# MCU_Module_V3.net
KiCad netlist of a schematic drawn in EAGLE
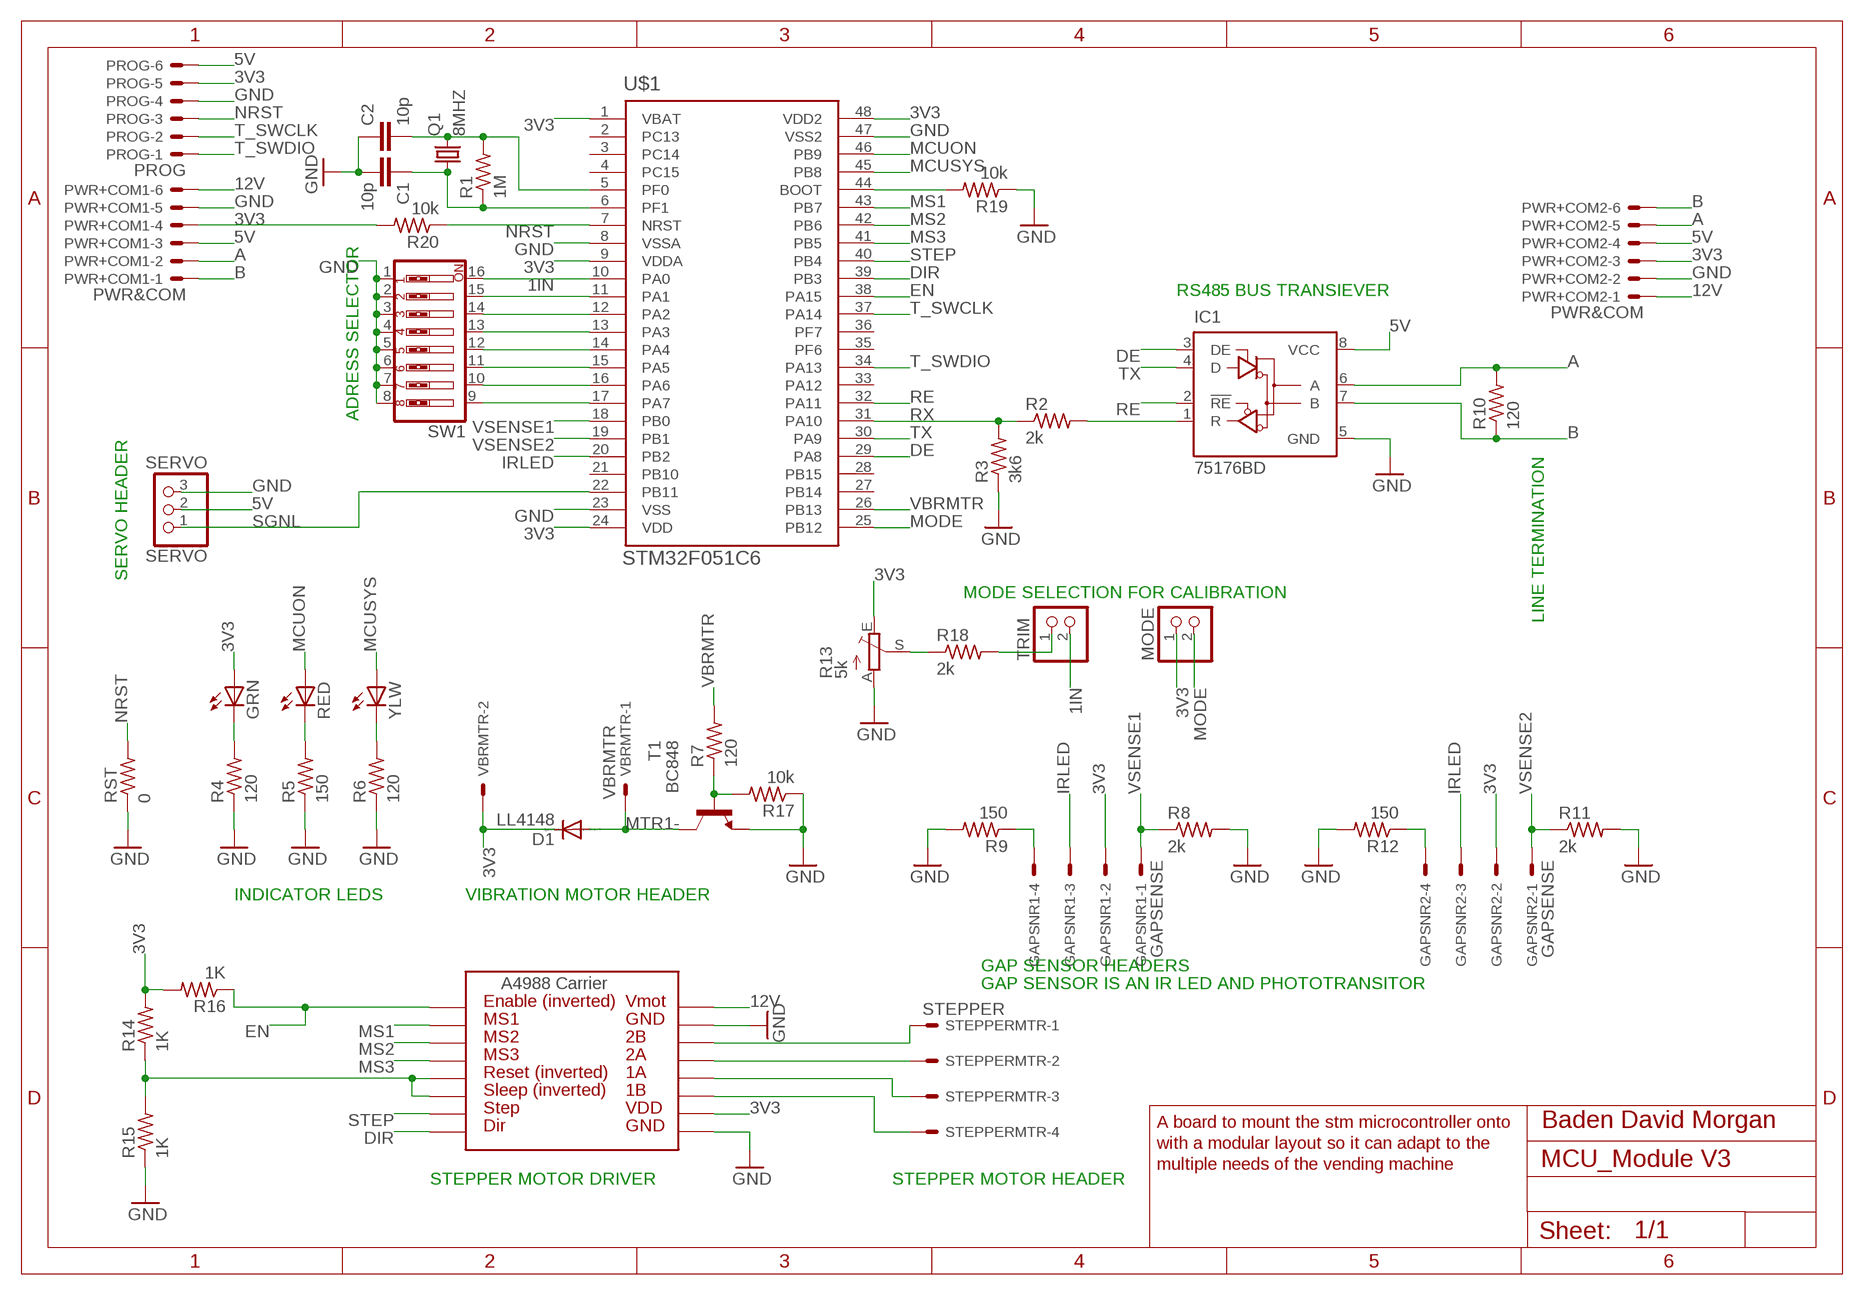
[diagram p0: schematic, sheet 1]

(export (version "E")
  (design (tool "Eeschema 10.0.6"))
  (components
    (comp (ref "C1")
      (value "10p")
      (footprint "eagle-import:C0805")
      (libsource (lib "eagle-import") (part "C-EUC0805"))
    )
    (comp (ref "C2")
      (value "10p")
      (footprint "eagle-import:C0805")
      (libsource (lib "eagle-import") (part "C-EUC0805"))
    )
    (comp (ref "D1")
      (value "LL4148")
      (footprint "eagle-import:SOD80C")
      (libsource (lib "eagle-import") (part "PMLL4150"))
    )
    (comp (ref "GAPSNR1")
      (value "GAPSENSE")
      (footprint "eagle-import:6410-04")
      (libsource (lib "eagle-import") (part "22-?-0427-2041"))
    )
    (comp (ref "GAPSNR2")
      (value "GAPSENSE")
      (footprint "eagle-import:6410-04")
      (libsource (lib "eagle-import") (part "22-?-0427-2041"))
    )
    (comp (ref "GRN")
      (value "LEDSML1206")
      (footprint "eagle-import:SML1206")
      (libsource (lib "eagle-import") (part "LEDSML1206"))
    )
    (comp (ref "IC1")
      (value "75176BD")
      (footprint "eagle-import:D_R-PDSO-G8")
      (libsource (lib "eagle-import") (part "75176AD"))
    )
    (comp (ref "MODE")
      (value "PINHD-1X2")
      (footprint "eagle-import:1X02")
      (libsource (lib "eagle-import") (part "PINHD-1X2"))
    )
    (comp (ref "PROG")
      (value "PROG")
      (footprint "eagle-import:6410-06")
      (libsource (lib "eagle-import") (part "22-?-0627-2061"))
    )
    (comp (ref "PWR+COM1")
      (value "PWR&COM")
      (footprint "eagle-import:7395-06")
      (libsource (lib "eagle-import") (part "22-?-0605-7068"))
    )
    (comp (ref "PWR+COM2")
      (value "PWR&COM")
      (footprint "eagle-import:7395-06")
      (libsource (lib "eagle-import") (part "22-?-0605-7068"))
    )
    (comp (ref "Q1")
      (value "8MHZ")
      (footprint "eagle-import:SM49")
      (libsource (lib "eagle-import") (part "CRYSTALSM49"))
    )
    (comp (ref "R1")
      (value "1M")
      (footprint "eagle-import:R0805")
      (libsource (lib "eagle-import") (part "R-US_R0805"))
    )
    (comp (ref "R2")
      (value "2k")
      (footprint "eagle-import:R0805")
      (libsource (lib "eagle-import") (part "resistor_R-US_R0805"))
    )
    (comp (ref "R3")
      (value "3k6")
      (footprint "eagle-import:R0805")
      (libsource (lib "eagle-import") (part "resistor_R-US_R0805"))
    )
    (comp (ref "R4")
      (value "120")
      (footprint "eagle-import:R0805")
      (libsource (lib "eagle-import") (part "R-US_R0805"))
    )
    (comp (ref "R5")
      (value "150")
      (footprint "eagle-import:R0805")
      (libsource (lib "eagle-import") (part "R-US_R0805"))
    )
    (comp (ref "R6")
      (value "120")
      (footprint "eagle-import:R0805")
      (libsource (lib "eagle-import") (part "R-US_R0805"))
    )
    (comp (ref "R7")
      (value "120")
      (footprint "eagle-import:R0805")
      (libsource (lib "eagle-import") (part "R-US_R0805"))
    )
    (comp (ref "R8")
      (value "2k")
      (footprint "eagle-import:R0805")
      (libsource (lib "eagle-import") (part "resistor_R-US_R0805"))
    )
    (comp (ref "R9")
      (value "150")
      (footprint "eagle-import:R0805")
      (libsource (lib "eagle-import") (part "R-US_R0805"))
    )
    (comp (ref "R10")
      (value "120")
      (footprint "eagle-import:R0805")
      (libsource (lib "eagle-import") (part "resistor_R-US_R0805"))
    )
    (comp (ref "R11")
      (value "2k")
      (footprint "eagle-import:R0805")
      (libsource (lib "eagle-import") (part "resistor_R-US_R0805"))
    )
    (comp (ref "R12")
      (value "150")
      (footprint "eagle-import:R0805")
      (libsource (lib "eagle-import") (part "R-US_R0805"))
    )
    (comp (ref "R13")
      (value "5k")
      (footprint "eagle-import:B25P")
      (libsource (lib "eagle-import") (part "TRIM_EU-B25P"))
    )
    (comp (ref "R14")
      (value "1K")
      (footprint "eagle-import:R0805")
      (libsource (lib "eagle-import") (part "R-US_R0805"))
    )
    (comp (ref "R15")
      (value "1K")
      (footprint "eagle-import:R0805")
      (libsource (lib "eagle-import") (part "R-US_R0805"))
    )
    (comp (ref "R16")
      (value "1K")
      (footprint "eagle-import:R0805")
      (libsource (lib "eagle-import") (part "R-US_R0805"))
    )
    (comp (ref "R17")
      (value "10k")
      (footprint "eagle-import:R0805")
      (libsource (lib "eagle-import") (part "R-US_R0805"))
    )
    (comp (ref "R18")
      (value "2k")
      (footprint "eagle-import:R0805")
      (libsource (lib "eagle-import") (part "resistor_R-US_R0805"))
    )
    (comp (ref "R19")
      (value "10k")
      (footprint "eagle-import:R0805")
      (libsource (lib "eagle-import") (part "R-US_R0805"))
    )
    (comp (ref "R20")
      (value "10k")
      (footprint "eagle-import:R0805")
      (libsource (lib "eagle-import") (part "R-US_R0805"))
    )
    (comp (ref "RED")
      (value "LEDSML1206")
      (footprint "eagle-import:SML1206")
      (libsource (lib "eagle-import") (part "LEDSML1206"))
    )
    (comp (ref "RST")
      (value "0")
      (footprint "eagle-import:R0805")
      (libsource (lib "eagle-import") (part "R-US_R0805"))
    )
    (comp (ref "SERVO")
      (value "SERVO")
      (footprint "eagle-import:1X03")
      (libsource (lib "eagle-import") (part "PINHD-1X3"))
    )
    (comp (ref "STEPPERMTR")
      (value "STEPPER")
      (footprint "eagle-import:6410-04")
      (libsource (lib "eagle-import") (part "22-?-0427-2041"))
    )
    (comp (ref "SW1")
      (value "SW_DIP-8")
      (footprint "eagle-import:EDG-08")
      (libsource (lib "eagle-import") (part "SW_DIP-8"))
    )
    (comp (ref "T1")
      (value "BC848")
      (footprint "eagle-import:SOT23")
      (libsource (lib "eagle-import") (part "BC848"))
    )
    (comp (ref "TRIM")
      (value "PINHD-1X2")
      (footprint "eagle-import:1X02")
      (libsource (lib "eagle-import") (part "PINHD-1X2"))
    )
    (comp (ref "U$1")
      (value "STM32F051C6")
      (footprint "eagle-import:QFP50P900X900X160-48N")
      (libsource (lib "eagle-import") (part "STM32F051C6"))
    )
    (comp (ref "U$2")
      (value "A4983CARRIER")
      (footprint "eagle-import:A4988BREAKOUT")
      (libsource (lib "eagle-import") (part "A4983CARRIER"))
    )
    (comp (ref "VBRMTR")
      (value "VBRMTR")
      (footprint "eagle-import:6410-02")
      (libsource (lib "eagle-import") (part "22-?-0227-2021"))
    )
    (comp (ref "YLW")
      (value "LEDSML1206")
      (footprint "eagle-import:SML1206")
      (libsource (lib "eagle-import") (part "LEDSML1206"))
    )
  )
  (nets
    (net (code "1") (name "/1IN") (class "Default")
      (node (ref "SW1") (pin "16") (pinfunction "16_16") (pintype "passive"))
      (node (ref "TRIM") (pin "2") (pinfunction "2_2") (pintype "passive"))
      (node (ref "U$1") (pin "10") (pinfunction "PA0_10") (pintype "bidirectional"))
    )
    (net (code "2") (name "/3V3") (class "Default")
      (node (ref "D1") (pin "C") (pinfunction "C_C") (pintype "passive"))
      (node (ref "GAPSNR1") (pin "2") (pinfunction "S_2") (pintype "passive"))
      (node (ref "GAPSNR2") (pin "2") (pinfunction "S_2") (pintype "passive"))
      (node (ref "GRN") (pin "A") (pinfunction "A_A") (pintype "passive"))
      (node (ref "MODE") (pin "1") (pinfunction "1_1") (pintype "passive"))
      (node (ref "PROG") (pin "5") (pinfunction "S_5") (pintype "passive"))
      (node (ref "PWR+COM1") (pin "4") (pinfunction "S_4") (pintype "passive"))
      (node (ref "PWR+COM2") (pin "3") (pinfunction "S_3") (pintype "passive"))
      (node (ref "R13") (pin "E") (pinfunction "E_E") (pintype "passive"))
      (node (ref "R14") (pin "2") (pinfunction "2_2") (pintype "passive"))
      (node (ref "R16") (pin "2") (pinfunction "2_2") (pintype "passive"))
      (node (ref "R20") (pin "2") (pinfunction "2_2") (pintype "passive"))
      (node (ref "U$1") (pin "1") (pinfunction "VBAT_1") (pintype "bidirectional"))
      (node (ref "U$1") (pin "24") (pinfunction "VDD_24") (pintype "bidirectional"))
      (node (ref "U$1") (pin "48") (pinfunction "VDD2_48") (pintype "bidirectional"))
      (node (ref "U$1") (pin "9") (pinfunction "VDDA_9") (pintype "bidirectional"))
      (node (ref "U$2") (pin "VDD") (pinfunction "VDD_VDD") (pintype "power_in"))
      (node (ref "VBRMTR") (pin "2") (pinfunction "S_2") (pintype "passive"))
    )
    (net (code "3") (name "/5V") (class "Default")
      (node (ref "IC1") (pin "8") (pinfunction "VCC_8") (pintype "power_in"))
      (node (ref "PROG") (pin "6") (pinfunction "S_6") (pintype "passive"))
      (node (ref "PWR+COM1") (pin "3") (pinfunction "S_3") (pintype "passive"))
      (node (ref "PWR+COM2") (pin "4") (pinfunction "S_4") (pintype "passive"))
      (node (ref "SERVO") (pin "2") (pinfunction "2_2") (pintype "passive"))
    )
    (net (code "4") (name "/12V") (class "Default")
      (node (ref "PWR+COM1") (pin "6") (pinfunction "S_6") (pintype "passive"))
      (node (ref "PWR+COM2") (pin "1") (pinfunction "S_1") (pintype "passive"))
      (node (ref "U$2") (pin "VMOT") (pinfunction "VMOT_VMOT") (pintype "power_in"))
    )
    (net (code "5") (name "/A") (class "Default")
      (node (ref "IC1") (pin "6") (pinfunction "A_6") (pintype "output"))
      (node (ref "PWR+COM1") (pin "2") (pinfunction "S_2") (pintype "passive"))
      (node (ref "PWR+COM2") (pin "5") (pinfunction "S_5") (pintype "passive"))
      (node (ref "R10") (pin "2") (pinfunction "2_2") (pintype "passive"))
    )
    (net (code "6") (name "/B") (class "Default")
      (node (ref "IC1") (pin "7") (pinfunction "B_7") (pintype "output"))
      (node (ref "PWR+COM1") (pin "1") (pinfunction "S_1") (pintype "passive"))
      (node (ref "PWR+COM2") (pin "6") (pinfunction "S_6") (pintype "passive"))
      (node (ref "R10") (pin "1") (pinfunction "1_1") (pintype "passive"))
    )
    (net (code "7") (name "/DE") (class "Default")
      (node (ref "IC1") (pin "3") (pinfunction "DE_3") (pintype "input"))
      (node (ref "U$1") (pin "29") (pinfunction "PA8_29") (pintype "bidirectional"))
    )
    (net (code "8") (name "/DIR") (class "Default")
      (node (ref "U$1") (pin "39") (pinfunction "PB3_39") (pintype "bidirectional"))
      (node (ref "U$2") (pin "DIR") (pinfunction "DIR_DIR") (pintype "input"))
    )
    (net (code "9") (name "/EN") (class "Default")
      (node (ref "R16") (pin "1") (pinfunction "1_1") (pintype "passive"))
      (node (ref "U$1") (pin "38") (pinfunction "PA15_38") (pintype "bidirectional"))
      (node (ref "U$2") (pin "EN") (pinfunction "EN_EN") (pintype "input"))
    )
    (net (code "10") (name "/IRLED") (class "Default")
      (node (ref "GAPSNR1") (pin "3") (pinfunction "S_3") (pintype "passive"))
      (node (ref "GAPSNR2") (pin "3") (pinfunction "S_3") (pintype "passive"))
      (node (ref "U$1") (pin "20") (pinfunction "PB2_20") (pintype "bidirectional"))
    )
    (net (code "11") (name "/MCUON") (class "Default")
      (node (ref "RED") (pin "A") (pinfunction "A_A") (pintype "passive"))
      (node (ref "U$1") (pin "46") (pinfunction "PB9_46") (pintype "bidirectional"))
    )
    (net (code "12") (name "/MCUSYS") (class "Default")
      (node (ref "U$1") (pin "45") (pinfunction "PB8_45") (pintype "bidirectional"))
      (node (ref "YLW") (pin "A") (pinfunction "A_A") (pintype "passive"))
    )
    (net (code "13") (name "/MODE") (class "Default")
      (node (ref "MODE") (pin "2") (pinfunction "2_2") (pintype "passive"))
      (node (ref "U$1") (pin "25") (pinfunction "PB12_25") (pintype "bidirectional"))
    )
    (net (code "14") (name "/MS1") (class "Default")
      (node (ref "U$1") (pin "43") (pinfunction "PB7_43") (pintype "bidirectional"))
      (node (ref "U$2") (pin "MS1") (pinfunction "MS1_MS1") (pintype "input"))
    )
    (net (code "15") (name "/MS2") (class "Default")
      (node (ref "U$1") (pin "42") (pinfunction "PB6_42") (pintype "bidirectional"))
      (node (ref "U$2") (pin "MS2") (pinfunction "MS2_MS2") (pintype "input"))
    )
    (net (code "16") (name "/MS3") (class "Default")
      (node (ref "U$1") (pin "41") (pinfunction "PB5_41") (pintype "bidirectional"))
      (node (ref "U$2") (pin "MS3") (pinfunction "MS3_MS3") (pintype "input"))
    )
    (net (code "17") (name "/MTR1-") (class "Default")
      (node (ref "D1") (pin "A") (pinfunction "A_A") (pintype "passive"))
      (node (ref "T1") (pin "3") (pinfunction "C_3") (pintype "passive"))
      (node (ref "VBRMTR") (pin "1") (pinfunction "S_1") (pintype "passive"))
    )
    (net (code "18") (name "/NRST") (class "Default")
      (node (ref "PROG") (pin "3") (pinfunction "S_3") (pintype "passive"))
      (node (ref "R20") (pin "1") (pinfunction "1_1") (pintype "passive"))
      (node (ref "RST") (pin "2") (pinfunction "2_2") (pintype "passive"))
      (node (ref "U$1") (pin "7") (pinfunction "NRST_7") (pintype "bidirectional"))
    )
    (net (code "19") (name "/RE") (class "Default")
      (node (ref "IC1") (pin "2") (pinfunction "~{RE}_2") (pintype "input"))
      (node (ref "U$1") (pin "32") (pinfunction "PA11_32") (pintype "bidirectional"))
    )
    (net (code "20") (name "/RX") (class "Default")
      (node (ref "R2") (pin "1") (pinfunction "1_1") (pintype "passive"))
      (node (ref "R3") (pin "2") (pinfunction "2_2") (pintype "passive"))
      (node (ref "U$1") (pin "31") (pinfunction "PA10_31") (pintype "bidirectional"))
    )
    (net (code "21") (name "/SGNL") (class "Default")
      (node (ref "SERVO") (pin "1") (pinfunction "1_1") (pintype "passive"))
      (node (ref "U$1") (pin "22") (pinfunction "PB11_22") (pintype "bidirectional"))
    )
    (net (code "22") (name "/STEP") (class "Default")
      (node (ref "U$1") (pin "40") (pinfunction "PB4_40") (pintype "bidirectional"))
      (node (ref "U$2") (pin "STEP") (pinfunction "STEP_STEP") (pintype "input"))
    )
    (net (code "23") (name "/TX") (class "Default")
      (node (ref "IC1") (pin "4") (pinfunction "D_4") (pintype "input"))
      (node (ref "U$1") (pin "30") (pinfunction "PA9_30") (pintype "bidirectional"))
    )
    (net (code "24") (name "/T_SWCLK") (class "Default")
      (node (ref "PROG") (pin "2") (pinfunction "S_2") (pintype "passive"))
      (node (ref "U$1") (pin "37") (pinfunction "PA14_37") (pintype "bidirectional"))
    )
    (net (code "25") (name "/T_SWDIO") (class "Default")
      (node (ref "PROG") (pin "1") (pinfunction "S_1") (pintype "passive"))
      (node (ref "U$1") (pin "34") (pinfunction "PA13_34") (pintype "bidirectional"))
    )
    (net (code "26") (name "/VBRMTR") (class "Default")
      (node (ref "R7") (pin "2") (pinfunction "2_2") (pintype "passive"))
      (node (ref "U$1") (pin "26") (pinfunction "PB13_26") (pintype "bidirectional"))
    )
    (net (code "27") (name "/VSENSE1") (class "Default")
      (node (ref "GAPSNR1") (pin "1") (pinfunction "S_1") (pintype "passive"))
      (node (ref "R8") (pin "1") (pinfunction "1_1") (pintype "passive"))
      (node (ref "U$1") (pin "18") (pinfunction "PB0_18") (pintype "bidirectional"))
    )
    (net (code "28") (name "/VSENSE2") (class "Default")
      (node (ref "GAPSNR2") (pin "1") (pinfunction "S_1") (pintype "passive"))
      (node (ref "R11") (pin "1") (pinfunction "1_1") (pintype "passive"))
      (node (ref "U$1") (pin "19") (pinfunction "PB1_19") (pintype "bidirectional"))
    )
    (net (code "29") (name "GND") (class "Default")
      (node (ref "C1") (pin "2") (pinfunction "2_2") (pintype "passive"))
      (node (ref "C2") (pin "1") (pinfunction "1_1") (pintype "passive"))
      (node (ref "IC1") (pin "5") (pinfunction "GND_5") (pintype "power_in"))
      (node (ref "PROG") (pin "4") (pinfunction "S_4") (pintype "passive"))
      (node (ref "PWR+COM1") (pin "5") (pinfunction "S_5") (pintype "passive"))
      (node (ref "PWR+COM2") (pin "2") (pinfunction "S_2") (pintype "passive"))
      (node (ref "R11") (pin "2") (pinfunction "2_2") (pintype "passive"))
      (node (ref "R12") (pin "2") (pinfunction "2_2") (pintype "passive"))
      (node (ref "R13") (pin "A") (pinfunction "A_A") (pintype "passive"))
      (node (ref "R15") (pin "1") (pinfunction "1_1") (pintype "passive"))
      (node (ref "R17") (pin "1") (pinfunction "1_1") (pintype "passive"))
      (node (ref "R19") (pin "1") (pinfunction "1_1") (pintype "passive"))
      (node (ref "R3") (pin "1") (pinfunction "1_1") (pintype "passive"))
      (node (ref "R4") (pin "1") (pinfunction "1_1") (pintype "passive"))
      (node (ref "R5") (pin "1") (pinfunction "1_1") (pintype "passive"))
      (node (ref "R6") (pin "1") (pinfunction "1_1") (pintype "passive"))
      (node (ref "R8") (pin "2") (pinfunction "2_2") (pintype "passive"))
      (node (ref "R9") (pin "2") (pinfunction "2_2") (pintype "passive"))
      (node (ref "RST") (pin "1") (pinfunction "1_1") (pintype "passive"))
      (node (ref "SERVO") (pin "3") (pinfunction "3_3") (pintype "passive"))
      (node (ref "SW1") (pin "1") (pinfunction "1_1") (pintype "passive"))
      (node (ref "SW1") (pin "2") (pinfunction "2_2") (pintype "passive"))
      (node (ref "SW1") (pin "3") (pinfunction "3_3") (pintype "passive"))
      (node (ref "SW1") (pin "4") (pinfunction "4_4") (pintype "passive"))
      (node (ref "SW1") (pin "5") (pinfunction "5_5") (pintype "passive"))
      (node (ref "SW1") (pin "6") (pinfunction "6_6") (pintype "passive"))
      (node (ref "SW1") (pin "7") (pinfunction "7_7") (pintype "passive"))
      (node (ref "SW1") (pin "8") (pinfunction "8_8") (pintype "passive"))
      (node (ref "T1") (pin "2") (pinfunction "E_2") (pintype "passive"))
      (node (ref "U$1") (pin "23") (pinfunction "VSS_23") (pintype "bidirectional"))
      (node (ref "U$1") (pin "47") (pinfunction "VSS2_47") (pintype "bidirectional"))
      (node (ref "U$1") (pin "8") (pinfunction "VSSA_8") (pintype "bidirectional"))
      (node (ref "U$2") (pin "GND") (pinfunction "GND_GND") (pintype "power_in"))
      (node (ref "U$2") (pin "GND@0") (pinfunction "GND_GND@0") (pintype "power_in"))
    )
    (net (code "30") (name "Net-(GAPSNR1D-S)") (class "Default")
      (node (ref "GAPSNR1") (pin "4") (pinfunction "S_4") (pintype "passive"))
      (node (ref "R9") (pin "1") (pinfunction "1_1") (pintype "passive"))
    )
    (net (code "31") (name "Net-(GAPSNR2D-S)") (class "Default")
      (node (ref "GAPSNR2") (pin "4") (pinfunction "S_4") (pintype "passive"))
      (node (ref "R12") (pin "1") (pinfunction "1_1") (pintype "passive"))
    )
    (net (code "32") (name "Net-(GRN-PadC)") (class "Default")
      (node (ref "GRN") (pin "C") (pinfunction "C_C") (pintype "passive"))
      (node (ref "R4") (pin "2") (pinfunction "2_2") (pintype "passive"))
    )
    (net (code "33") (name "Net-(IC1-R)") (class "Default")
      (node (ref "IC1") (pin "1") (pinfunction "R_1") (pintype "input"))
      (node (ref "R2") (pin "2") (pinfunction "2_2") (pintype "passive"))
    )
    (net (code "34") (name "Net-(R5-Pad2)") (class "Default")
      (node (ref "R5") (pin "2") (pinfunction "2_2") (pintype "passive"))
      (node (ref "RED") (pin "C") (pinfunction "C_C") (pintype "passive"))
    )
    (net (code "35") (name "Net-(R6-Pad2)") (class "Default")
      (node (ref "R6") (pin "2") (pinfunction "2_2") (pintype "passive"))
      (node (ref "YLW") (pin "C") (pinfunction "C_C") (pintype "passive"))
    )
    (net (code "36") (name "Net-(R13-PadS)") (class "Default")
      (node (ref "R13") (pin "S") (pinfunction "S_S") (pintype "passive"))
      (node (ref "R18") (pin "1") (pinfunction "1_1") (pintype "passive"))
    )
    (net (code "37") (name "Net-(R18-Pad2)") (class "Default")
      (node (ref "R18") (pin "2") (pinfunction "2_2") (pintype "passive"))
      (node (ref "TRIM") (pin "1") (pinfunction "1_1") (pintype "passive"))
    )
    (net (code "38") (name "Net-(STEPPERMTRA-S)") (class "Default")
      (node (ref "STEPPERMTR") (pin "1") (pinfunction "S_1") (pintype "passive"))
      (node (ref "U$2") (pin "2B") (pinfunction "2B_2B") (pintype "output"))
    )
    (net (code "39") (name "Net-(STEPPERMTRB-S)") (class "Default")
      (node (ref "STEPPERMTR") (pin "2") (pinfunction "S_2") (pintype "passive"))
      (node (ref "U$2") (pin "2A") (pinfunction "2A_2A") (pintype "output"))
    )
    (net (code "40") (name "Net-(STEPPERMTRC-S)") (class "Default")
      (node (ref "STEPPERMTR") (pin "3") (pinfunction "S_3") (pintype "passive"))
      (node (ref "U$2") (pin "1A") (pinfunction "1A_1A") (pintype "output"))
    )
    (net (code "41") (name "Net-(STEPPERMTRD-S)") (class "Default")
      (node (ref "STEPPERMTR") (pin "4") (pinfunction "S_4") (pintype "passive"))
      (node (ref "U$2") (pin "1B") (pinfunction "1B_1B") (pintype "output"))
    )
    (net (code "42") (name "Net-(T1-B)") (class "Default")
      (node (ref "R17") (pin "2") (pinfunction "2_2") (pintype "passive"))
      (node (ref "R7") (pin "1") (pinfunction "1_1") (pintype "passive"))
      (node (ref "T1") (pin "1") (pinfunction "B_1") (pintype "passive"))
    )
    (net (code "43") (name "Net-(U$1-BOOT)") (class "Default")
      (node (ref "R19") (pin "2") (pinfunction "2_2") (pintype "passive"))
      (node (ref "U$1") (pin "44") (pinfunction "BOOT_44") (pintype "bidirectional"))
    )
    (net (code "44") (name "Net-(U$1-PA1)") (class "Default")
      (node (ref "SW1") (pin "15") (pinfunction "15_15") (pintype "passive"))
      (node (ref "U$1") (pin "11") (pinfunction "PA1_11") (pintype "bidirectional"))
    )
    (net (code "45") (name "Net-(U$1-PA2)") (class "Default")
      (node (ref "SW1") (pin "14") (pinfunction "14_14") (pintype "passive"))
      (node (ref "U$1") (pin "12") (pinfunction "PA2_12") (pintype "bidirectional"))
    )
    (net (code "46") (name "Net-(U$1-PA3)") (class "Default")
      (node (ref "SW1") (pin "13") (pinfunction "13_13") (pintype "passive"))
      (node (ref "U$1") (pin "13") (pinfunction "PA3_13") (pintype "bidirectional"))
    )
    (net (code "47") (name "Net-(U$1-PA4)") (class "Default")
      (node (ref "SW1") (pin "12") (pinfunction "12_12") (pintype "passive"))
      (node (ref "U$1") (pin "14") (pinfunction "PA4_14") (pintype "bidirectional"))
    )
    (net (code "48") (name "Net-(U$1-PA5)") (class "Default")
      (node (ref "SW1") (pin "11") (pinfunction "11_11") (pintype "passive"))
      (node (ref "U$1") (pin "15") (pinfunction "PA5_15") (pintype "bidirectional"))
    )
    (net (code "49") (name "Net-(U$1-PA6)") (class "Default")
      (node (ref "SW1") (pin "10") (pinfunction "10_10") (pintype "passive"))
      (node (ref "U$1") (pin "16") (pinfunction "PA6_16") (pintype "bidirectional"))
    )
    (net (code "50") (name "Net-(U$1-PA7)") (class "Default")
      (node (ref "SW1") (pin "9") (pinfunction "9_9") (pintype "passive"))
      (node (ref "U$1") (pin "17") (pinfunction "PA7_17") (pintype "bidirectional"))
    )
    (net (code "51") (name "Net-(U$1-PF0)") (class "Default")
      (node (ref "C2") (pin "2") (pinfunction "2_2") (pintype "passive"))
      (node (ref "Q1") (pin "2") (pinfunction "2_2") (pintype "passive"))
      (node (ref "R1") (pin "2") (pinfunction "2_2") (pintype "passive"))
      (node (ref "U$1") (pin "5") (pinfunction "PF0_5") (pintype "bidirectional"))
    )
    (net (code "52") (name "Net-(U$1-PF1)") (class "Default")
      (node (ref "C1") (pin "1") (pinfunction "1_1") (pintype "passive"))
      (node (ref "Q1") (pin "1") (pinfunction "1_1") (pintype "passive"))
      (node (ref "R1") (pin "1") (pinfunction "1_1") (pintype "passive"))
      (node (ref "U$1") (pin "6") (pinfunction "PF1_6") (pintype "bidirectional"))
    )
    (net (code "53") (name "Net-(U$2-SLEEP)") (class "Default")
      (node (ref "R14") (pin "1") (pinfunction "1_1") (pintype "passive"))
      (node (ref "R15") (pin "2") (pinfunction "2_2") (pintype "passive"))
      (node (ref "U$2") (pin "RST") (pinfunction "RST_RST") (pintype "input"))
      (node (ref "U$2") (pin "SLP") (pinfunction "SLEEP_SLP") (pintype "input"))
    )
    (net (code "54") (name "unconnected-(U$1-PA12-Pad33)") (class "Default")
      (node (ref "U$1") (pin "33") (pinfunction "PA12_33") (pintype "bidirectional"))
    )
    (net (code "55") (name "unconnected-(U$1-PB10-Pad21)") (class "Default")
      (node (ref "U$1") (pin "21") (pinfunction "PB10_21") (pintype "bidirectional"))
    )
    (net (code "56") (name "unconnected-(U$1-PB14-Pad27)") (class "Default")
      (node (ref "U$1") (pin "27") (pinfunction "PB14_27") (pintype "bidirectional"))
    )
    (net (code "57") (name "unconnected-(U$1-PB15-Pad28)") (class "Default")
      (node (ref "U$1") (pin "28") (pinfunction "PB15_28") (pintype "bidirectional"))
    )
    (net (code "58") (name "unconnected-(U$1-PC13-Pad2)") (class "Default")
      (node (ref "U$1") (pin "2") (pinfunction "PC13_2") (pintype "bidirectional"))
    )
    (net (code "59") (name "unconnected-(U$1-PC14-Pad3)") (class "Default")
      (node (ref "U$1") (pin "3") (pinfunction "PC14_3") (pintype "bidirectional"))
    )
    (net (code "60") (name "unconnected-(U$1-PC15-Pad4)") (class "Default")
      (node (ref "U$1") (pin "4") (pinfunction "PC15_4") (pintype "bidirectional"))
    )
    (net (code "61") (name "unconnected-(U$1-PF6-Pad35)") (class "Default")
      (node (ref "U$1") (pin "35") (pinfunction "PF6_35") (pintype "bidirectional"))
    )
    (net (code "62") (name "unconnected-(U$1-PF7-Pad36)") (class "Default")
      (node (ref "U$1") (pin "36") (pinfunction "PF7_36") (pintype "bidirectional"))
    )
  )
)
